# octanis_eps_compact.net
KiCad netlist of a schematic drawn in EAGLE
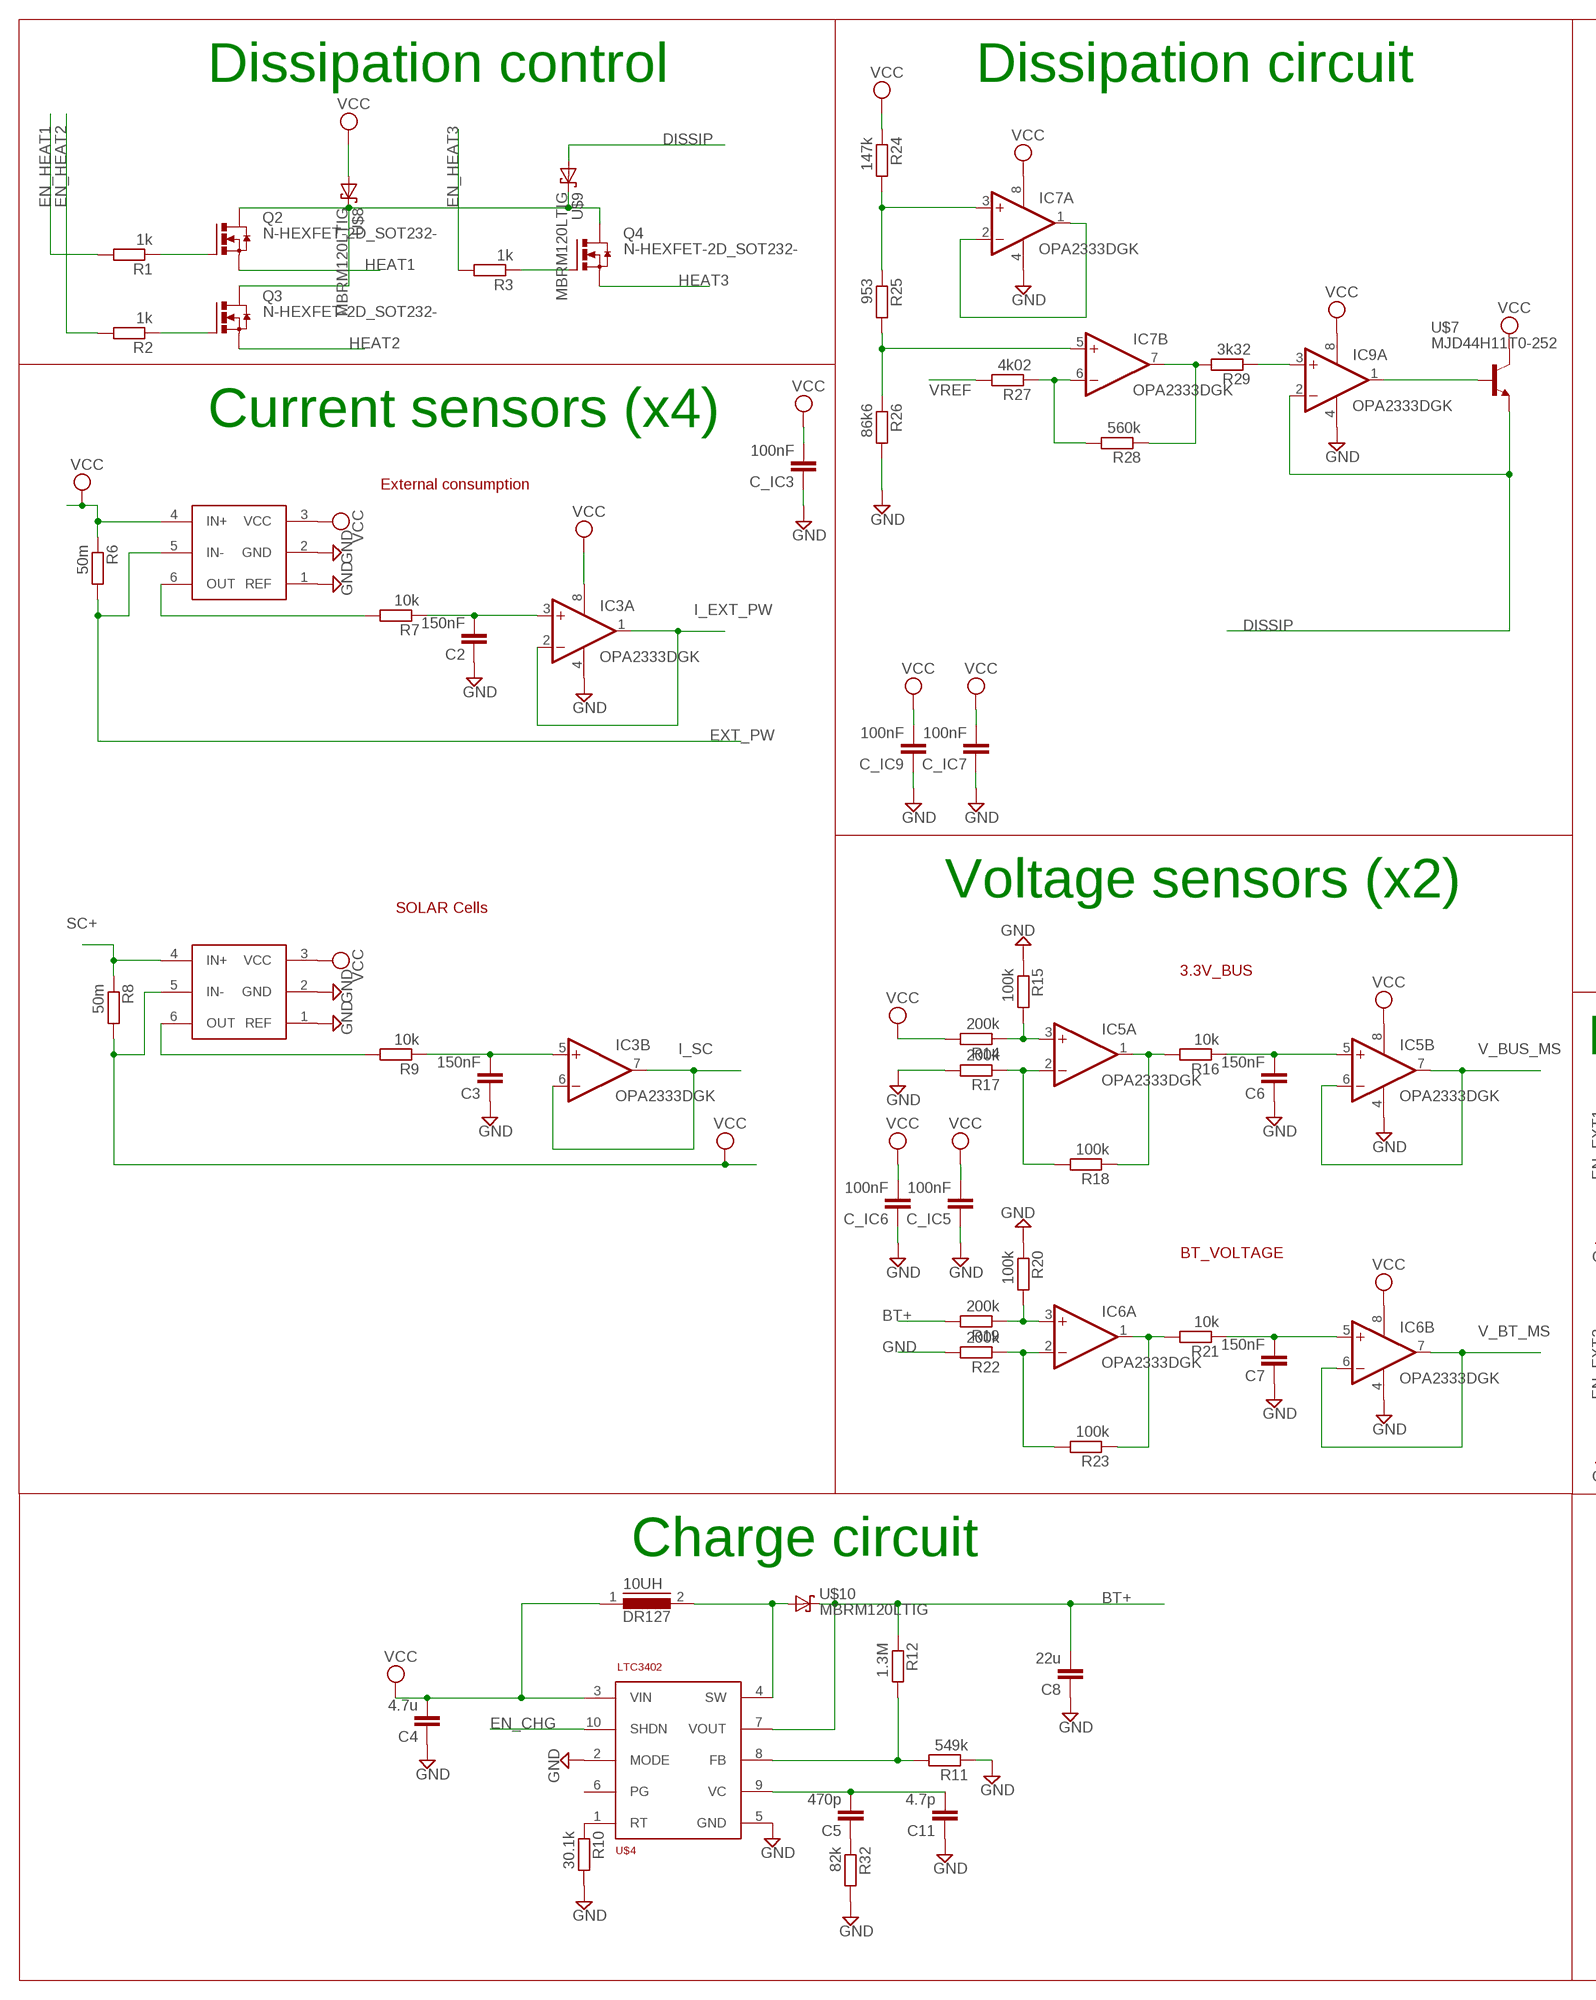
[diagram p0: schematic, sheet 1, part 1 of 2]
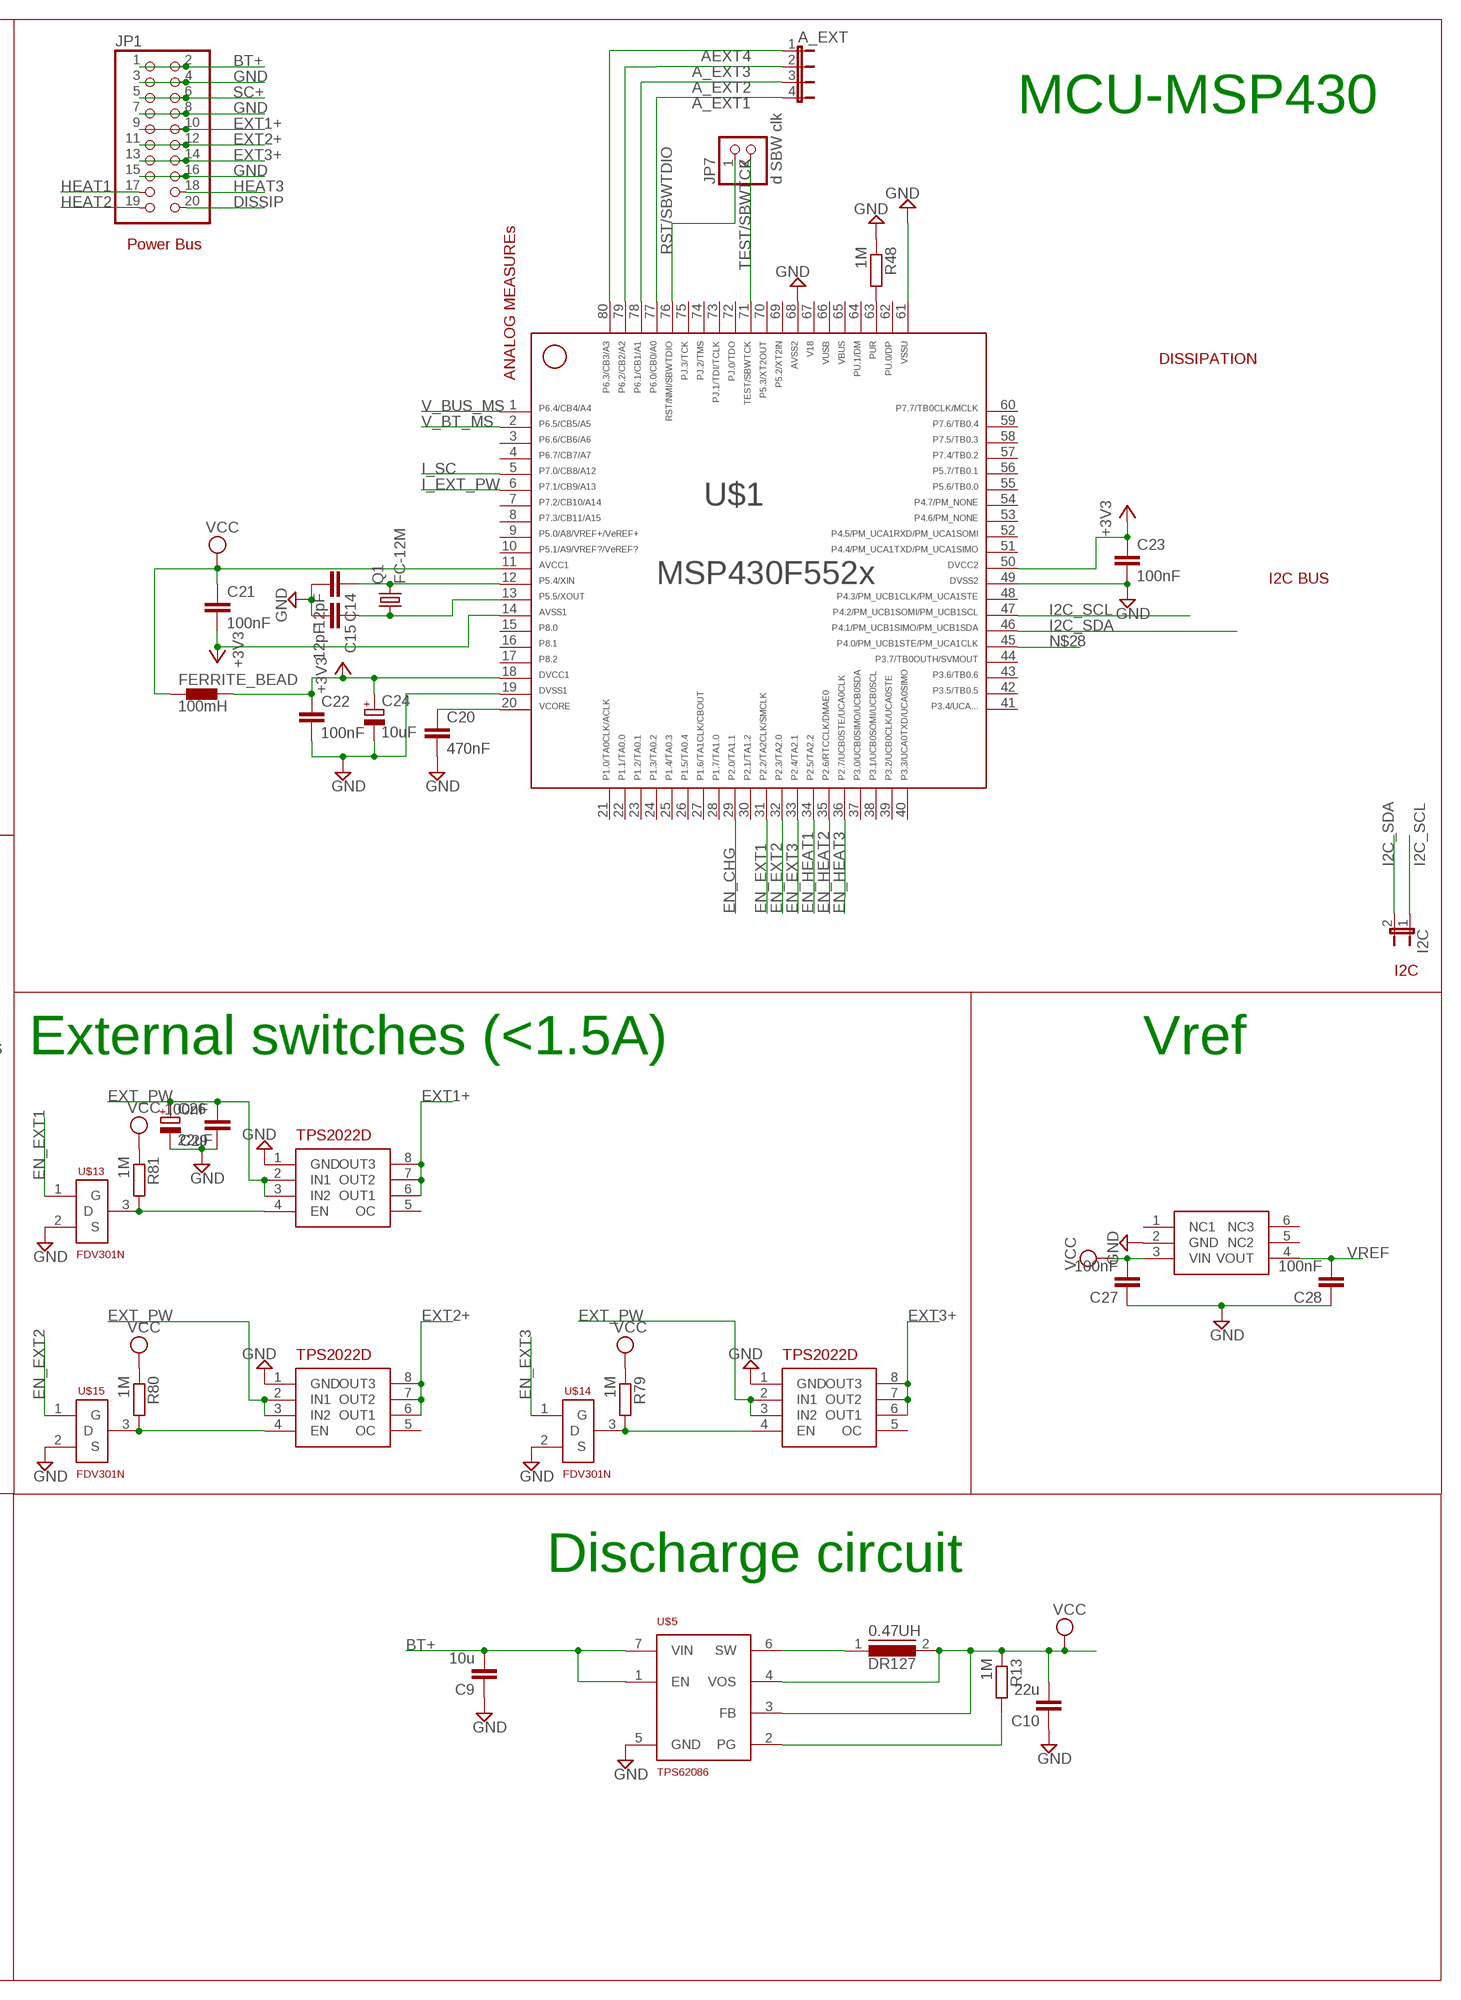
[diagram p1: schematic, sheet 1, part 2 of 2]

(export (version "E")
  (design (tool "Eeschema 10.0.6"))
  (components
    (comp (ref "0.47UH")
      (value "DR127")
      (footprint "eagle-import:DR127")
      (libsource (lib "eagle-import") (part "DR127"))
    )
    (comp (ref "10UH")
      (value "DR127")
      (footprint "eagle-import:DR127")
      (libsource (lib "eagle-import") (part "DR127"))
    )
    (comp (ref "A_EXT")
      (value "JP4E")
      (footprint "eagle-import:JP4")
      (libsource (lib "eagle-import") (part "JP4E"))
    )
    (comp (ref "C2")
      (value "150nF")
      (footprint "eagle-import:C0603")
      (libsource (lib "eagle-import") (part "C-EUC0603"))
    )
    (comp (ref "C3")
      (value "150nF")
      (footprint "eagle-import:C0603")
      (libsource (lib "eagle-import") (part "C-EUC0603"))
    )
    (comp (ref "C4")
      (value "4.7u")
      (footprint "eagle-import:C1206")
      (libsource (lib "eagle-import") (part "C-EUC1206"))
    )
    (comp (ref "C5")
      (value "470p")
      (footprint "eagle-import:C0603")
      (libsource (lib "eagle-import") (part "C-EUC0603"))
    )
    (comp (ref "C6")
      (value "150nF")
      (footprint "eagle-import:C0603")
      (libsource (lib "eagle-import") (part "C-EUC0603"))
    )
    (comp (ref "C7")
      (value "150nF")
      (footprint "eagle-import:C0603")
      (libsource (lib "eagle-import") (part "C-EUC0603"))
    )
    (comp (ref "C8")
      (value "22u")
      (footprint "eagle-import:C0603")
      (libsource (lib "eagle-import") (part "C-EUC0603"))
    )
    (comp (ref "C9")
      (value "10u")
      (footprint "eagle-import:C1206")
      (libsource (lib "eagle-import") (part "C-EUC1206"))
    )
    (comp (ref "C10")
      (value "22u")
      (footprint "eagle-import:C1206")
      (libsource (lib "eagle-import") (part "C-EUC1206"))
    )
    (comp (ref "C11")
      (value "4.7p")
      (footprint "eagle-import:C0603")
      (libsource (lib "eagle-import") (part "C-EUC0603"))
    )
    (comp (ref "C14")
      (value "12pF")
      (footprint "eagle-import:C0603")
      (libsource (lib "eagle-import") (part "C-EUC0603"))
    )
    (comp (ref "C15")
      (value "12pF")
      (footprint "eagle-import:C0603")
      (libsource (lib "eagle-import") (part "C-EUC0603"))
    )
    (comp (ref "C20")
      (value "470nF")
      (footprint "eagle-import:C0603")
      (libsource (lib "eagle-import") (part "C-EUC0603"))
    )
    (comp (ref "C21")
      (value "100nF")
      (footprint "eagle-import:C0603")
      (libsource (lib "eagle-import") (part "C-EUC0603"))
    )
    (comp (ref "C22")
      (value "100nF")
      (footprint "eagle-import:C0603")
      (libsource (lib "eagle-import") (part "C-EUC0603"))
    )
    (comp (ref "C23")
      (value "100nF")
      (footprint "eagle-import:C0603")
      (libsource (lib "eagle-import") (part "C-EUC0603"))
    )
    (comp (ref "C24")
      (value "10uF")
      (footprint "eagle-import:A_3216-18R")
      (libsource (lib "eagle-import") (part "CPOL-EUA/3216-18R"))
    )
    (comp (ref "C26")
      (value "22uF")
      (footprint "eagle-import:A_3216-18R")
      (libsource (lib "eagle-import") (part "CPOL-EUA/3216-18R"))
    )
    (comp (ref "C27")
      (value "100nF")
      (footprint "eagle-import:C0603")
      (libsource (lib "eagle-import") (part "C-EUC0603"))
    )
    (comp (ref "C28")
      (value "100nF")
      (footprint "eagle-import:C0603")
      (libsource (lib "eagle-import") (part "C-EUC0603"))
    )
    (comp (ref "C29")
      (value "100nF")
      (footprint "eagle-import:C0603")
      (libsource (lib "eagle-import") (part "C-EUC0603"))
    )
    (comp (ref "C_IC3")
      (value "100nF")
      (footprint "eagle-import:C0603")
      (libsource (lib "eagle-import") (part "C-EUC0603"))
    )
    (comp (ref "C_IC5")
      (value "100nF")
      (footprint "eagle-import:C0603")
      (libsource (lib "eagle-import") (part "C-EUC0603"))
    )
    (comp (ref "C_IC6")
      (value "100nF")
      (footprint "eagle-import:C0603")
      (libsource (lib "eagle-import") (part "C-EUC0603"))
    )
    (comp (ref "C_IC7")
      (value "100nF")
      (footprint "eagle-import:C0603")
      (libsource (lib "eagle-import") (part "C-EUC0603"))
    )
    (comp (ref "C_IC9")
      (value "100nF")
      (footprint "eagle-import:C0603")
      (libsource (lib "eagle-import") (part "C-EUC0603"))
    )
    (comp (ref "FERRITE_BEAD")
      (value "100mH")
      (footprint "eagle-import:0402")
      (libsource (lib "eagle-import") (part "BLM15HD601SN1"))
    )
    (comp (ref "I2C")
      (value "JP1E")
      (footprint "eagle-import:JP1")
      (libsource (lib "eagle-import") (part "JP1E"))
    )
    (comp (ref "IC3")
      (value "OPA2333DGK")
      (footprint "eagle-import:MSOP08")
      (libsource (lib "eagle-import") (part "OPA2333DGK"))
    )
    (comp (ref "IC5")
      (value "OPA2333DGK")
      (footprint "eagle-import:MSOP08")
      (libsource (lib "eagle-import") (part "OPA2333DGK"))
    )
    (comp (ref "IC6")
      (value "OPA2333DGK")
      (footprint "eagle-import:MSOP08")
      (libsource (lib "eagle-import") (part "OPA2333DGK"))
    )
    (comp (ref "IC7")
      (value "OPA2333DGK")
      (footprint "eagle-import:MSOP08")
      (libsource (lib "eagle-import") (part "OPA2333DGK"))
    )
    (comp (ref "IC9")
      (value "OPA2333DGK")
      (footprint "eagle-import:MSOP08")
      (libsource (lib "eagle-import") (part "OPA2333DGK"))
    )
    (comp (ref "JP1")
      (value "PINHD-2X10")
      (footprint "eagle-import:2X10")
      (libsource (lib "eagle-import") (part "PINHD-2X10"))
    )
    (comp (ref "JP7")
      (value "d SBW clk")
      (footprint "eagle-import:1X02")
      (libsource (lib "eagle-import") (part "PINHD-1X2"))
    )
    (comp (ref "Q1")
      (value "FC-12M")
      (footprint "eagle-import:FC-12M")
      (libsource (lib "eagle-import") (part "FC-12M"))
    )
    (comp (ref "Q2")
      (value "N-HEXFET-2D_SOT232-")
      (footprint "eagle-import:SOT223")
      (libsource (lib "eagle-import") (part "N-HEXFET-2D_?-SOT232"))
    )
    (comp (ref "Q3")
      (value "N-HEXFET-2D_SOT232-")
      (footprint "eagle-import:SOT223")
      (libsource (lib "eagle-import") (part "N-HEXFET-2D_?-SOT232"))
    )
    (comp (ref "Q4")
      (value "N-HEXFET-2D_SOT232-")
      (footprint "eagle-import:SOT223")
      (libsource (lib "eagle-import") (part "N-HEXFET-2D_?-SOT232"))
    )
    (comp (ref "R1")
      (value "1k")
      (footprint "eagle-import:R0603")
      (libsource (lib "eagle-import") (part "R-EU_R0603"))
    )
    (comp (ref "R2")
      (value "1k")
      (footprint "eagle-import:R0603")
      (libsource (lib "eagle-import") (part "R-EU_R0603"))
    )
    (comp (ref "R3")
      (value "1k")
      (footprint "eagle-import:R0603")
      (libsource (lib "eagle-import") (part "R-EU_R0603"))
    )
    (comp (ref "R6")
      (value "50m")
      (footprint "eagle-import:R1206")
      (libsource (lib "eagle-import") (part "R-EU_R1206"))
    )
    (comp (ref "R7")
      (value "10k")
      (footprint "eagle-import:R0603")
      (libsource (lib "eagle-import") (part "R-EU_R0603"))
    )
    (comp (ref "R8")
      (value "50m")
      (footprint "eagle-import:R1206")
      (libsource (lib "eagle-import") (part "R-EU_R1206"))
    )
    (comp (ref "R9")
      (value "10k")
      (footprint "eagle-import:R0603")
      (libsource (lib "eagle-import") (part "R-EU_R0603"))
    )
    (comp (ref "R10")
      (value "30.1k")
      (footprint "eagle-import:R0603")
      (libsource (lib "eagle-import") (part "R-EU_R0603"))
    )
    (comp (ref "R11")
      (value "549k")
      (footprint "eagle-import:R0603")
      (libsource (lib "eagle-import") (part "R-EU_R0603"))
    )
    (comp (ref "R12")
      (value "1.3M")
      (footprint "eagle-import:R0603")
      (libsource (lib "eagle-import") (part "R-EU_R0603"))
    )
    (comp (ref "R13")
      (value "1M")
      (footprint "eagle-import:R0603")
      (libsource (lib "eagle-import") (part "R-EU_R0603"))
    )
    (comp (ref "R14")
      (value "200k")
      (footprint "eagle-import:R0603")
      (libsource (lib "eagle-import") (part "R-EU_R0603"))
    )
    (comp (ref "R15")
      (value "100k")
      (footprint "eagle-import:R0603")
      (libsource (lib "eagle-import") (part "R-EU_R0603"))
    )
    (comp (ref "R16")
      (value "10k")
      (footprint "eagle-import:R0603")
      (libsource (lib "eagle-import") (part "R-EU_R0603"))
    )
    (comp (ref "R17")
      (value "200k")
      (footprint "eagle-import:R0603")
      (libsource (lib "eagle-import") (part "R-EU_R0603"))
    )
    (comp (ref "R18")
      (value "100k")
      (footprint "eagle-import:R0603")
      (libsource (lib "eagle-import") (part "R-EU_R0603"))
    )
    (comp (ref "R19")
      (value "200k")
      (footprint "eagle-import:R0603")
      (libsource (lib "eagle-import") (part "R-EU_R0603"))
    )
    (comp (ref "R20")
      (value "100k")
      (footprint "eagle-import:R0603")
      (libsource (lib "eagle-import") (part "R-EU_R0603"))
    )
    (comp (ref "R21")
      (value "10k")
      (footprint "eagle-import:R0603")
      (libsource (lib "eagle-import") (part "R-EU_R0603"))
    )
    (comp (ref "R22")
      (value "200k")
      (footprint "eagle-import:R0603")
      (libsource (lib "eagle-import") (part "R-EU_R0603"))
    )
    (comp (ref "R23")
      (value "100k")
      (footprint "eagle-import:R0603")
      (libsource (lib "eagle-import") (part "R-EU_R0603"))
    )
    (comp (ref "R24")
      (value "147k")
      (footprint "eagle-import:R0603")
      (libsource (lib "eagle-import") (part "R-EU_R0603"))
    )
    (comp (ref "R25")
      (value "953")
      (footprint "eagle-import:R0603")
      (libsource (lib "eagle-import") (part "R-EU_R0603"))
    )
    (comp (ref "R26")
      (value "86k6")
      (footprint "eagle-import:R0603")
      (libsource (lib "eagle-import") (part "R-EU_R0603"))
    )
    (comp (ref "R27")
      (value "4k02")
      (footprint "eagle-import:R0603")
      (libsource (lib "eagle-import") (part "R-EU_R0603"))
    )
    (comp (ref "R28")
      (value "560k")
      (footprint "eagle-import:R0603")
      (libsource (lib "eagle-import") (part "R-EU_R0603"))
    )
    (comp (ref "R29")
      (value "3k32")
      (footprint "eagle-import:R0603")
      (libsource (lib "eagle-import") (part "R-EU_R0603"))
    )
    (comp (ref "R32")
      (value "82k")
      (footprint "eagle-import:R0603")
      (libsource (lib "eagle-import") (part "R-EU_R0603"))
    )
    (comp (ref "R48")
      (value "1M")
      (footprint "eagle-import:R0603")
      (libsource (lib "eagle-import") (part "R-EU_R0603"))
    )
    (comp (ref "R79")
      (value "1M")
      (footprint "eagle-import:R0603")
      (libsource (lib "eagle-import") (part "R-EU_R0603"))
    )
    (comp (ref "R80")
      (value "1M")
      (footprint "eagle-import:R0603")
      (libsource (lib "eagle-import") (part "R-EU_R0603"))
    )
    (comp (ref "R81")
      (value "1M")
      (footprint "eagle-import:R0603")
      (libsource (lib "eagle-import") (part "R-EU_R0603"))
    )
    (comp (ref "U$1")
      (value "F552X---PN80")
      (footprint "eagle-import:PN80")
      (libsource (lib "eagle-import") (part "F552X---PN80"))
    )
    (comp (ref "U$2")
      (value "INA213")
      (footprint "eagle-import:SC70-6")
      (libsource (lib "eagle-import") (part "INA213"))
    )
    (comp (ref "U$3")
      (value "INA213")
      (footprint "eagle-import:SC70-6")
      (libsource (lib "eagle-import") (part "INA213"))
    )
    (comp (ref "U$4")
      (value "LTC3402")
      (footprint "eagle-import:MSOP10")
      (libsource (lib "eagle-import") (part "LTC3402"))
    )
    (comp (ref "U$5")
      (value "TPS62086")
      (footprint "eagle-import:QFN-7")
      (libsource (lib "eagle-import") (part "TPS62086"))
    )
    (comp (ref "U$7")
      (value "MJD44H11T0-252")
      (footprint "eagle-import:TO252")
      (libsource (lib "eagle-import") (part "MJD44H11T0-252"))
    )
    (comp (ref "U$8")
      (value "MBRM120LTIG")
      (footprint "eagle-import:DO216AA")
      (libsource (lib "eagle-import") (part "MBRM120LTIG"))
    )
    (comp (ref "U$9")
      (value "MBRM120LTIG")
      (footprint "eagle-import:DO216AA")
      (libsource (lib "eagle-import") (part "MBRM120LTIG"))
    )
    (comp (ref "U$10")
      (value "MBRM120LTIG")
      (footprint "eagle-import:DO216AA")
      (libsource (lib "eagle-import") (part "MBRM120LTIG"))
    )
    (comp (ref "U$13")
      (value "FDV301N")
      (footprint "eagle-import:SOT23")
      (libsource (lib "eagle-import") (part "FDV301N"))
    )
    (comp (ref "U$14")
      (value "FDV301N")
      (footprint "eagle-import:SOT23")
      (libsource (lib "eagle-import") (part "FDV301N"))
    )
    (comp (ref "U$15")
      (value "FDV301N")
      (footprint "eagle-import:SOT23")
      (libsource (lib "eagle-import") (part "FDV301N"))
    )
    (comp (ref "U$16")
      (value "TPS2022D")
      (footprint "eagle-import:SO8")
      (libsource (lib "eagle-import") (part "TPS2022D"))
    )
    (comp (ref "U$17")
      (value "TPS2022D")
      (footprint "eagle-import:SO8")
      (libsource (lib "eagle-import") (part "TPS2022D"))
    )
    (comp (ref "U$18")
      (value "TPS2022D")
      (footprint "eagle-import:SO8")
      (libsource (lib "eagle-import") (part "TPS2022D"))
    )
    (comp (ref "U$19")
      (value "ADR127B")
      (footprint "eagle-import:TSOT23-6")
      (libsource (lib "eagle-import") (part "ADR127B"))
    )
  )
  (nets
    (net (code "1") (name "+3V3") (class "Default")
      (node (ref "C21") (pin "2") (pinfunction "2_2") (pintype "passive"))
      (node (ref "C22") (pin "1") (pinfunction "1_1") (pintype "passive"))
      (node (ref "C23") (pin "1") (pinfunction "1_1") (pintype "passive"))
      (node (ref "C24") (pin "+") (pinfunction "+_+") (pintype "passive"))
      (node (ref "FERRITE_BEAD") (pin "2") (pinfunction "2_2") (pintype "passive"))
      (node (ref "U$1") (pin "14") (pinfunction "14_14") (pintype "power_in"))
      (node (ref "U$1") (pin "18") (pinfunction "18_18") (pintype "power_in"))
      (node (ref "U$1") (pin "50") (pinfunction "50_50") (pintype "power_in"))
    )
    (net (code "2") (name "/65") (class "Default")
      (node (ref "U$1") (pin "65") (pinfunction "65_65") (pintype "power_in"))
    )
    (net (code "3") (name "/66") (class "Default")
      (node (ref "U$1") (pin "66") (pinfunction "66_66") (pintype "power_in"))
    )
    (net (code "4") (name "/67") (class "Default")
      (node (ref "U$1") (pin "67") (pinfunction "67_67") (pintype "power_in"))
    )
    (net (code "5") (name "/AEXT4") (class "Default")
      (node (ref "A_EXT") (pin "1") (pinfunction "1_1") (pintype "passive"))
      (node (ref "U$1") (pin "80") (pinfunction "80_80") (pintype "bidirectional"))
    )
    (net (code "6") (name "/A_EXT1") (class "Default")
      (node (ref "A_EXT") (pin "4") (pinfunction "4_4") (pintype "passive"))
      (node (ref "U$1") (pin "77") (pinfunction "77_77") (pintype "bidirectional"))
    )
    (net (code "7") (name "/A_EXT2") (class "Default")
      (node (ref "A_EXT") (pin "3") (pinfunction "3_3") (pintype "passive"))
      (node (ref "U$1") (pin "78") (pinfunction "78_78") (pintype "bidirectional"))
    )
    (net (code "8") (name "/A_EXT3") (class "Default")
      (node (ref "A_EXT") (pin "2") (pinfunction "2_2") (pintype "passive"))
      (node (ref "U$1") (pin "79") (pinfunction "79_79") (pintype "bidirectional"))
    )
    (net (code "9") (name "/BT+") (class "Default")
      (node (ref "C8") (pin "2") (pinfunction "2_2") (pintype "passive"))
      (node (ref "C9") (pin "2") (pinfunction "2_2") (pintype "passive"))
      (node (ref "JP1") (pin "1") (pinfunction "1_1") (pintype "passive"))
      (node (ref "JP1") (pin "2") (pinfunction "2_2") (pintype "passive"))
      (node (ref "R12") (pin "1") (pinfunction "1_1") (pintype "passive"))
      (node (ref "R19") (pin "2") (pinfunction "2_2") (pintype "passive"))
      (node (ref "U$10") (pin "C") (pinfunction "K_C") (pintype "passive"))
      (node (ref "U$4") (pin "7") (pinfunction "VOUT_7") (pintype "bidirectional"))
      (node (ref "U$5") (pin "1") (pinfunction "EN_1") (pintype "bidirectional"))
      (node (ref "U$5") (pin "7") (pinfunction "VIN_7") (pintype "bidirectional"))
    )
    (net (code "10") (name "/DISSIP") (class "Default")
      (node (ref "IC9") (pin "2") (pinfunction "-IN_2") (pintype "input"))
      (node (ref "JP1") (pin "20") (pinfunction "20_20") (pintype "passive"))
      (node (ref "U$7") (pin "3") (pinfunction "E_3") (pintype "passive"))
      (node (ref "U$9") (pin "A") (pinfunction "A_A") (pintype "passive"))
    )
    (net (code "11") (name "/EN_CHG") (class "Default")
      (node (ref "U$1") (pin "29") (pinfunction "29_29") (pintype "bidirectional"))
      (node (ref "U$4") (pin "10") (pinfunction "SHDN_10") (pintype "bidirectional"))
    )
    (net (code "12") (name "/EN_EXT1") (class "Default")
      (node (ref "U$1") (pin "31") (pinfunction "31_31") (pintype "bidirectional"))
      (node (ref "U$13") (pin "1") (pinfunction "G_1") (pintype "bidirectional"))
    )
    (net (code "13") (name "/EN_EXT2") (class "Default")
      (node (ref "U$1") (pin "32") (pinfunction "32_32") (pintype "bidirectional"))
      (node (ref "U$15") (pin "1") (pinfunction "G_1") (pintype "bidirectional"))
    )
    (net (code "14") (name "/EN_EXT3") (class "Default")
      (node (ref "U$1") (pin "33") (pinfunction "33_33") (pintype "bidirectional"))
      (node (ref "U$14") (pin "1") (pinfunction "G_1") (pintype "bidirectional"))
    )
    (net (code "15") (name "/EN_HEAT1") (class "Default")
      (node (ref "R1") (pin "2") (pinfunction "2_2") (pintype "passive"))
      (node (ref "U$1") (pin "34") (pinfunction "34_34") (pintype "bidirectional"))
    )
    (net (code "16") (name "/EN_HEAT2") (class "Default")
      (node (ref "R2") (pin "2") (pinfunction "2_2") (pintype "passive"))
      (node (ref "U$1") (pin "35") (pinfunction "35_35") (pintype "bidirectional"))
    )
    (net (code "17") (name "/EN_HEAT3") (class "Default")
      (node (ref "R3") (pin "2") (pinfunction "2_2") (pintype "passive"))
      (node (ref "U$1") (pin "36") (pinfunction "36_36") (pintype "bidirectional"))
    )
    (net (code "18") (name "/EXT1+") (class "Default")
      (node (ref "JP1") (pin "10") (pinfunction "10_10") (pintype "passive"))
      (node (ref "JP1") (pin "9") (pinfunction "9_9") (pintype "passive"))
      (node (ref "U$16") (pin "6") (pinfunction "OUT1_6") (pintype "bidirectional"))
      (node (ref "U$16") (pin "7") (pinfunction "OUT2_7") (pintype "bidirectional"))
      (node (ref "U$16") (pin "8") (pinfunction "OUT3_8") (pintype "bidirectional"))
    )
    (net (code "19") (name "/EXT2+") (class "Default")
      (node (ref "JP1") (pin "11") (pinfunction "11_11") (pintype "passive"))
      (node (ref "JP1") (pin "12") (pinfunction "12_12") (pintype "passive"))
      (node (ref "U$17") (pin "6") (pinfunction "OUT1_6") (pintype "bidirectional"))
      (node (ref "U$17") (pin "7") (pinfunction "OUT2_7") (pintype "bidirectional"))
      (node (ref "U$17") (pin "8") (pinfunction "OUT3_8") (pintype "bidirectional"))
    )
    (net (code "20") (name "/EXT3+") (class "Default")
      (node (ref "JP1") (pin "13") (pinfunction "13_13") (pintype "passive"))
      (node (ref "JP1") (pin "14") (pinfunction "14_14") (pintype "passive"))
      (node (ref "U$18") (pin "6") (pinfunction "OUT1_6") (pintype "bidirectional"))
      (node (ref "U$18") (pin "7") (pinfunction "OUT2_7") (pintype "bidirectional"))
      (node (ref "U$18") (pin "8") (pinfunction "OUT3_8") (pintype "bidirectional"))
    )
    (net (code "21") (name "/EXT_PW") (class "Default")
      (node (ref "C26") (pin "+") (pinfunction "+_+") (pintype "passive"))
      (node (ref "C29") (pin "2") (pinfunction "2_2") (pintype "passive"))
      (node (ref "R6") (pin "2") (pinfunction "2_2") (pintype "passive"))
      (node (ref "U$16") (pin "2") (pinfunction "IN1_2") (pintype "bidirectional"))
      (node (ref "U$16") (pin "3") (pinfunction "IN2_3") (pintype "bidirectional"))
      (node (ref "U$17") (pin "2") (pinfunction "IN1_2") (pintype "bidirectional"))
      (node (ref "U$17") (pin "3") (pinfunction "IN2_3") (pintype "bidirectional"))
      (node (ref "U$18") (pin "2") (pinfunction "IN1_2") (pintype "bidirectional"))
      (node (ref "U$18") (pin "3") (pinfunction "IN2_3") (pintype "bidirectional"))
      (node (ref "U$2") (pin "5") (pinfunction "IN-_5") (pintype "bidirectional"))
    )
    (net (code "22") (name "/HEAT1") (class "Default")
      (node (ref "JP1") (pin "17") (pinfunction "17_17") (pintype "passive"))
      (node (ref "Q2") (pin "3") (pinfunction "S_3") (pintype "passive"))
    )
    (net (code "23") (name "/HEAT2") (class "Default")
      (node (ref "JP1") (pin "19") (pinfunction "19_19") (pintype "passive"))
      (node (ref "Q3") (pin "3") (pinfunction "S_3") (pintype "passive"))
    )
    (net (code "24") (name "/HEAT3") (class "Default")
      (node (ref "JP1") (pin "18") (pinfunction "18_18") (pintype "passive"))
      (node (ref "Q4") (pin "3") (pinfunction "S_3") (pintype "passive"))
    )
    (net (code "25") (name "/I2C_SCL") (class "Default")
      (node (ref "I2C") (pin "1") (pinfunction "1_1") (pintype "passive"))
      (node (ref "U$1") (pin "47") (pinfunction "47_47") (pintype "bidirectional"))
    )
    (net (code "26") (name "/I2C_SDA") (class "Default")
      (node (ref "I2C") (pin "2") (pinfunction "2_2") (pintype "passive"))
      (node (ref "U$1") (pin "46") (pinfunction "46_46") (pintype "bidirectional"))
    )
    (net (code "27") (name "/I_EXT_PW") (class "Default")
      (node (ref "IC3") (pin "1") (pinfunction "OUT_1") (pintype "output"))
      (node (ref "IC3") (pin "2") (pinfunction "-IN_2") (pintype "input"))
      (node (ref "U$1") (pin "6") (pinfunction "6_6") (pintype "bidirectional"))
    )
    (net (code "28") (name "/I_SC") (class "Default")
      (node (ref "IC3") (pin "6") (pinfunction "-IN_6") (pintype "input"))
      (node (ref "IC3") (pin "7") (pinfunction "OUT_7") (pintype "output"))
      (node (ref "U$1") (pin "5") (pinfunction "5_5") (pintype "bidirectional"))
    )
    (net (code "29") (name "/N$28") (class "Default")
      (node (ref "U$1") (pin "45") (pinfunction "45_45") (pintype "bidirectional"))
    )
    (net (code "30") (name "/RST{slash}SBWTDIO") (class "Default")
      (node (ref "JP7") (pin "1") (pinfunction "1_1") (pintype "passive"))
      (node (ref "U$1") (pin "76") (pinfunction "76_76") (pintype "bidirectional"))
    )
    (net (code "31") (name "/SC+") (class "Default")
      (node (ref "JP1") (pin "5") (pinfunction "5_5") (pintype "passive"))
      (node (ref "JP1") (pin "6") (pinfunction "6_6") (pintype "passive"))
      (node (ref "R8") (pin "1") (pinfunction "1_1") (pintype "passive"))
      (node (ref "U$3") (pin "4") (pinfunction "IN+_4") (pintype "bidirectional"))
    )
    (net (code "32") (name "/TEST{slash}SBWTCK") (class "Default")
      (node (ref "JP7") (pin "2") (pinfunction "2_2") (pintype "passive"))
      (node (ref "U$1") (pin "71") (pinfunction "71_71") (pintype "input"))
    )
    (net (code "33") (name "/VREF") (class "Default")
      (node (ref "C28") (pin "2") (pinfunction "2_2") (pintype "passive"))
      (node (ref "R27") (pin "2") (pinfunction "2_2") (pintype "passive"))
      (node (ref "U$19") (pin "4") (pinfunction "VOUT_4") (pintype "bidirectional"))
    )
    (net (code "34") (name "/V_BT_MS") (class "Default")
      (node (ref "IC6") (pin "6") (pinfunction "-IN_6") (pintype "input"))
      (node (ref "IC6") (pin "7") (pinfunction "OUT_7") (pintype "output"))
      (node (ref "U$1") (pin "2") (pinfunction "2_2") (pintype "bidirectional"))
    )
    (net (code "35") (name "/V_BUS_MS") (class "Default")
      (node (ref "IC5") (pin "6") (pinfunction "-IN_6") (pintype "input"))
      (node (ref "IC5") (pin "7") (pinfunction "OUT_7") (pintype "output"))
      (node (ref "U$1") (pin "1") (pinfunction "1_1") (pintype "bidirectional"))
    )
    (net (code "36") (name "GND") (class "Default")
      (node (ref "C10") (pin "1") (pinfunction "1_1") (pintype "passive"))
      (node (ref "C11") (pin "1") (pinfunction "1_1") (pintype "passive"))
      (node (ref "C14") (pin "2") (pinfunction "2_2") (pintype "passive"))
      (node (ref "C15") (pin "2") (pinfunction "2_2") (pintype "passive"))
      (node (ref "C2") (pin "1") (pinfunction "1_1") (pintype "passive"))
      (node (ref "C20") (pin "2") (pinfunction "2_2") (pintype "passive"))
      (node (ref "C22") (pin "2") (pinfunction "2_2") (pintype "passive"))
      (node (ref "C23") (pin "2") (pinfunction "2_2") (pintype "passive"))
      (node (ref "C24") (pin "-") (pinfunction "-_-") (pintype "passive"))
      (node (ref "C26") (pin "-") (pinfunction "-_-") (pintype "passive"))
      (node (ref "C27") (pin "1") (pinfunction "1_1") (pintype "passive"))
      (node (ref "C28") (pin "1") (pinfunction "1_1") (pintype "passive"))
      (node (ref "C29") (pin "1") (pinfunction "1_1") (pintype "passive"))
      (node (ref "C3") (pin "1") (pinfunction "1_1") (pintype "passive"))
      (node (ref "C4") (pin "1") (pinfunction "1_1") (pintype "passive"))
      (node (ref "C6") (pin "1") (pinfunction "1_1") (pintype "passive"))
      (node (ref "C7") (pin "1") (pinfunction "1_1") (pintype "passive"))
      (node (ref "C8") (pin "1") (pinfunction "1_1") (pintype "passive"))
      (node (ref "C9") (pin "1") (pinfunction "1_1") (pintype "passive"))
      (node (ref "C_IC3") (pin "1") (pinfunction "1_1") (pintype "passive"))
      (node (ref "C_IC5") (pin "1") (pinfunction "1_1") (pintype "passive"))
      (node (ref "C_IC6") (pin "1") (pinfunction "1_1") (pintype "passive"))
      (node (ref "C_IC7") (pin "1") (pinfunction "1_1") (pintype "passive"))
      (node (ref "C_IC9") (pin "1") (pinfunction "1_1") (pintype "passive"))
      (node (ref "IC3") (pin "4") (pinfunction "V-_4") (pintype "power_in"))
      (node (ref "IC5") (pin "4") (pinfunction "V-_4") (pintype "power_in"))
      (node (ref "IC6") (pin "4") (pinfunction "V-_4") (pintype "power_in"))
      (node (ref "IC7") (pin "4") (pinfunction "V-_4") (pintype "power_in"))
      (node (ref "IC9") (pin "4") (pinfunction "V-_4") (pintype "power_in"))
      (node (ref "JP1") (pin "15") (pinfunction "15_15") (pintype "passive"))
      (node (ref "JP1") (pin "16") (pinfunction "16_16") (pintype "passive"))
      (node (ref "JP1") (pin "3") (pinfunction "3_3") (pintype "passive"))
      (node (ref "JP1") (pin "4") (pinfunction "4_4") (pintype "passive"))
      (node (ref "JP1") (pin "7") (pinfunction "7_7") (pintype "passive"))
      (node (ref "JP1") (pin "8") (pinfunction "8_8") (pintype "passive"))
      (node (ref "R10") (pin "2") (pinfunction "2_2") (pintype "passive"))
      (node (ref "R11") (pin "1") (pinfunction "1_1") (pintype "passive"))
      (node (ref "R15") (pin "1") (pinfunction "1_1") (pintype "passive"))
      (node (ref "R17") (pin "2") (pinfunction "2_2") (pintype "passive"))
      (node (ref "R20") (pin "1") (pinfunction "1_1") (pintype "passive"))
      (node (ref "R22") (pin "2") (pinfunction "2_2") (pintype "passive"))
      (node (ref "R26") (pin "2") (pinfunction "2_2") (pintype "passive"))
      (node (ref "R32") (pin "2") (pinfunction "2_2") (pintype "passive"))
      (node (ref "R48") (pin "1") (pinfunction "1_1") (pintype "passive"))
      (node (ref "U$1") (pin "19") (pinfunction "19_19") (pintype "power_in"))
      (node (ref "U$1") (pin "49") (pinfunction "49_49") (pintype "power_in"))
      (node (ref "U$1") (pin "61") (pinfunction "61_61") (pintype "power_in"))
      (node (ref "U$1") (pin "68") (pinfunction "68_68") (pintype "power_in"))
      (node (ref "U$13") (pin "2") (pinfunction "S_2") (pintype "bidirectional"))
      (node (ref "U$14") (pin "2") (pinfunction "S_2") (pintype "bidirectional"))
      (node (ref "U$15") (pin "2") (pinfunction "S_2") (pintype "bidirectional"))
      (node (ref "U$16") (pin "1") (pinfunction "GND_1") (pintype "bidirectional"))
      (node (ref "U$17") (pin "1") (pinfunction "GND_1") (pintype "bidirectional"))
      (node (ref "U$18") (pin "1") (pinfunction "GND_1") (pintype "bidirectional"))
      (node (ref "U$19") (pin "2") (pinfunction "GND_2") (pintype "bidirectional"))
      (node (ref "U$2") (pin "1") (pinfunction "REF_1") (pintype "bidirectional"))
      (node (ref "U$2") (pin "2") (pinfunction "GND_2") (pintype "bidirectional"))
      (node (ref "U$3") (pin "1") (pinfunction "REF_1") (pintype "bidirectional"))
      (node (ref "U$3") (pin "2") (pinfunction "GND_2") (pintype "bidirectional"))
      (node (ref "U$4") (pin "2") (pinfunction "MODE_2") (pintype "bidirectional"))
      (node (ref "U$4") (pin "5") (pinfunction "GND_5") (pintype "bidirectional"))
      (node (ref "U$5") (pin "5") (pinfunction "GND_5") (pintype "bidirectional"))
    )
    (net (code "37") (name "Net-(C5-Pad1)") (class "Default")
      (node (ref "C5") (pin "1") (pinfunction "1_1") (pintype "passive"))
      (node (ref "R32") (pin "1") (pinfunction "1_1") (pintype "passive"))
    )
    (net (code "38") (name "Net-(C14-Pad1)") (class "Default")
      (node (ref "C14") (pin "1") (pinfunction "1_1") (pintype "passive"))
      (node (ref "Q1") (pin "2") (pinfunction "2_2") (pintype "passive"))
      (node (ref "U$1") (pin "12") (pinfunction "12_12") (pintype "bidirectional"))
    )
    (net (code "39") (name "Net-(C15-Pad1)") (class "Default")
      (node (ref "C15") (pin "1") (pinfunction "1_1") (pintype "passive"))
      (node (ref "Q1") (pin "1") (pinfunction "1_1") (pintype "passive"))
      (node (ref "U$1") (pin "13") (pinfunction "13_13") (pintype "bidirectional"))
    )
    (net (code "40") (name "Net-(C20-Pad1)") (class "Default")
      (node (ref "C20") (pin "1") (pinfunction "1_1") (pintype "passive"))
      (node (ref "U$1") (pin "20") (pinfunction "20_20") (pintype "power_in"))
    )
    (net (code "41") (name "Net-(IC3A-+IN)") (class "Default")
      (node (ref "C2") (pin "2") (pinfunction "2_2") (pintype "passive"))
      (node (ref "IC3") (pin "3") (pinfunction "+IN_3") (pintype "input"))
      (node (ref "R7") (pin "1") (pinfunction "1_1") (pintype "passive"))
    )
    (net (code "42") (name "Net-(IC3B-+IN)") (class "Default")
      (node (ref "C3") (pin "2") (pinfunction "2_2") (pintype "passive"))
      (node (ref "IC3") (pin "5") (pinfunction "+IN_5") (pintype "input"))
      (node (ref "R9") (pin "1") (pinfunction "1_1") (pintype "passive"))
    )
    (net (code "43") (name "Net-(IC5A-+IN)") (class "Default")
      (node (ref "IC5") (pin "3") (pinfunction "+IN_3") (pintype "input"))
      (node (ref "R14") (pin "1") (pinfunction "1_1") (pintype "passive"))
      (node (ref "R15") (pin "2") (pinfunction "2_2") (pintype "passive"))
    )
    (net (code "44") (name "Net-(IC5A--IN)") (class "Default")
      (node (ref "IC5") (pin "2") (pinfunction "-IN_2") (pintype "input"))
      (node (ref "R17") (pin "1") (pinfunction "1_1") (pintype "passive"))
      (node (ref "R18") (pin "2") (pinfunction "2_2") (pintype "passive"))
    )
    (net (code "45") (name "Net-(IC5A-OUT)") (class "Default")
      (node (ref "IC5") (pin "1") (pinfunction "OUT_1") (pintype "output"))
      (node (ref "R16") (pin "2") (pinfunction "2_2") (pintype "passive"))
      (node (ref "R18") (pin "1") (pinfunction "1_1") (pintype "passive"))
    )
    (net (code "46") (name "Net-(IC5B-+IN)") (class "Default")
      (node (ref "C6") (pin "2") (pinfunction "2_2") (pintype "passive"))
      (node (ref "IC5") (pin "5") (pinfunction "+IN_5") (pintype "input"))
      (node (ref "R16") (pin "1") (pinfunction "1_1") (pintype "passive"))
    )
    (net (code "47") (name "Net-(IC6A-+IN)") (class "Default")
      (node (ref "IC6") (pin "3") (pinfunction "+IN_3") (pintype "input"))
      (node (ref "R19") (pin "1") (pinfunction "1_1") (pintype "passive"))
      (node (ref "R20") (pin "2") (pinfunction "2_2") (pintype "passive"))
    )
    (net (code "48") (name "Net-(IC6A--IN)") (class "Default")
      (node (ref "IC6") (pin "2") (pinfunction "-IN_2") (pintype "input"))
      (node (ref "R22") (pin "1") (pinfunction "1_1") (pintype "passive"))
      (node (ref "R23") (pin "2") (pinfunction "2_2") (pintype "passive"))
    )
    (net (code "49") (name "Net-(IC6A-OUT)") (class "Default")
      (node (ref "IC6") (pin "1") (pinfunction "OUT_1") (pintype "output"))
      (node (ref "R21") (pin "2") (pinfunction "2_2") (pintype "passive"))
      (node (ref "R23") (pin "1") (pinfunction "1_1") (pintype "passive"))
    )
    (net (code "50") (name "Net-(IC6B-+IN)") (class "Default")
      (node (ref "C7") (pin "2") (pinfunction "2_2") (pintype "passive"))
      (node (ref "IC6") (pin "5") (pinfunction "+IN_5") (pintype "input"))
      (node (ref "R21") (pin "1") (pinfunction "1_1") (pintype "passive"))
    )
    (net (code "51") (name "Net-(IC7A-+IN)") (class "Default")
      (node (ref "IC7") (pin "3") (pinfunction "+IN_3") (pintype "input"))
      (node (ref "R24") (pin "2") (pinfunction "2_2") (pintype "passive"))
      (node (ref "R25") (pin "1") (pinfunction "1_1") (pintype "passive"))
    )
    (net (code "52") (name "Net-(IC7A--IN)") (class "Default")
      (node (ref "IC7") (pin "1") (pinfunction "OUT_1") (pintype "output"))
      (node (ref "IC7") (pin "2") (pinfunction "-IN_2") (pintype "input"))
    )
    (net (code "53") (name "Net-(IC7B-+IN)") (class "Default")
      (node (ref "IC7") (pin "5") (pinfunction "+IN_5") (pintype "input"))
      (node (ref "R25") (pin "2") (pinfunction "2_2") (pintype "passive"))
      (node (ref "R26") (pin "1") (pinfunction "1_1") (pintype "passive"))
    )
    (net (code "54") (name "Net-(IC7B--IN)") (class "Default")
      (node (ref "IC7") (pin "6") (pinfunction "-IN_6") (pintype "input"))
      (node (ref "R27") (pin "1") (pinfunction "1_1") (pintype "passive"))
      (node (ref "R28") (pin "2") (pinfunction "2_2") (pintype "passive"))
    )
    (net (code "55") (name "Net-(IC7B-OUT)") (class "Default")
      (node (ref "IC7") (pin "7") (pinfunction "OUT_7") (pintype "output"))
      (node (ref "R28") (pin "1") (pinfunction "1_1") (pintype "passive"))
      (node (ref "R29") (pin "2") (pinfunction "2_2") (pintype "passive"))
    )
    (net (code "56") (name "Net-(IC9A-+IN)") (class "Default")
      (node (ref "IC9") (pin "3") (pinfunction "+IN_3") (pintype "input"))
      (node (ref "R29") (pin "1") (pinfunction "1_1") (pintype "passive"))
    )
    (net (code "57") (name "Net-(IC9A-OUT)") (class "Default")
      (node (ref "IC9") (pin "1") (pinfunction "OUT_1") (pintype "output"))
      (node (ref "U$7") (pin "1") (pinfunction "B_1") (pintype "passive"))
    )
    (net (code "58") (name "Net-(Q2-G)") (class "Default")
      (node (ref "Q2") (pin "1") (pinfunction "G_1") (pintype "passive"))
      (node (ref "R1") (pin "1") (pinfunction "1_1") (pintype "passive"))
    )
    (net (code "59") (name "Net-(Q3-G)") (class "Default")
      (node (ref "Q3") (pin "1") (pinfunction "G_1") (pintype "passive"))
      (node (ref "R2") (pin "1") (pinfunction "1_1") (pintype "passive"))
    )
    (net (code "60") (name "Net-(Q4-G)") (class "Default")
      (node (ref "Q4") (pin "1") (pinfunction "G_1") (pintype "passive"))
      (node (ref "R3") (pin "1") (pinfunction "1_1") (pintype "passive"))
    )
    (net (code "61") (name "Net-(R48-Pad2)") (class "Default")
      (node (ref "R48") (pin "2") (pinfunction "2_2") (pintype "passive"))
      (node (ref "U$1") (pin "63") (pinfunction "63_63") (pintype "bidirectional"))
    )
    (net (code "62") (name "Net-(U$2-OUT)") (class "Default")
      (node (ref "R7") (pin "2") (pinfunction "2_2") (pintype "passive"))
      (node (ref "U$2") (pin "6") (pinfunction "OUT_6") (pintype "bidirectional"))
    )
    (net (code "63") (name "Net-(U$3-OUT)") (class "Default")
      (node (ref "R9") (pin "2") (pinfunction "2_2") (pintype "passive"))
      (node (ref "U$3") (pin "6") (pinfunction "OUT_6") (pintype "bidirectional"))
    )
    (net (code "64") (name "Net-(U$4-FB)") (class "Default")
      (node (ref "R11") (pin "2") (pinfunction "2_2") (pintype "passive"))
      (node (ref "R12") (pin "2") (pinfunction "2_2") (pintype "passive"))
      (node (ref "U$4") (pin "8") (pinfunction "FB_8") (pintype "bidirectional"))
    )
    (net (code "65") (name "Net-(U$4-RT)") (class "Default")
      (node (ref "R10") (pin "1") (pinfunction "1_1") (pintype "passive"))
      (node (ref "U$4") (pin "1") (pinfunction "RT_1") (pintype "bidirectional"))
    )
    (net (code "66") (name "Net-(U$4-SW)") (class "Default")
      (node (ref "10UH") (pin "2") (pinfunction "2_2") (pintype "passive"))
      (node (ref "U$10") (pin "A") (pinfunction "A_A") (pintype "passive"))
      (node (ref "U$4") (pin "4") (pinfunction "SW_4") (pintype "bidirectional"))
    )
    (net (code "67") (name "Net-(U$4-VC)") (class "Default")
      (node (ref "C11") (pin "2") (pinfunction "2_2") (pintype "passive"))
      (node (ref "C5") (pin "2") (pinfunction "2_2") (pintype "passive"))
      (node (ref "U$4") (pin "9") (pinfunction "VC_9") (pintype "bidirectional"))
    )
    (net (code "68") (name "Net-(U$5-PG)") (class "Default")
      (node (ref "R13") (pin "2") (pinfunction "2_2") (pintype "passive"))
      (node (ref "U$5") (pin "2") (pinfunction "PG_2") (pintype "bidirectional"))
    )
    (net (code "69") (name "Net-(U$5-SW)") (class "Default")
      (node (ref "0.47UH") (pin "1") (pinfunction "1_1") (pintype "passive"))
      (node (ref "U$5") (pin "6") (pinfunction "SW_6") (pintype "bidirectional"))
    )
    (net (code "70") (name "Net-(U$8-K)") (class "Default")
      (node (ref "Q2") (pin "2") (pinfunction "D_2") (pintype "passive"))
      (node (ref "Q2") (pin "4") (pinfunction "D_4") (pintype "passive"))
      (node (ref "Q3") (pin "2") (pinfunction "D_2") (pintype "passive"))
      (node (ref "Q3") (pin "4") (pinfunction "D_4") (pintype "passive"))
      (node (ref "Q4") (pin "2") (pinfunction "D_2") (pintype "passive"))
      (node (ref "Q4") (pin "4") (pinfunction "D_4") (pintype "passive"))
      (node (ref "U$8") (pin "C") (pinfunction "K_C") (pintype "passive"))
      (node (ref "U$9") (pin "C") (pinfunction "K_C") (pintype "passive"))
    )
    (net (code "71") (name "Net-(U$13-D)") (class "Default")
      (node (ref "R81") (pin "2") (pinfunction "2_2") (pintype "passive"))
      (node (ref "U$13") (pin "3") (pinfunction "D_3") (pintype "bidirectional"))
      (node (ref "U$16") (pin "4") (pinfunction "EN_4") (pintype "bidirectional"))
    )
    (net (code "72") (name "Net-(U$14-D)") (class "Default")
      (node (ref "R79") (pin "2") (pinfunction "2_2") (pintype "passive"))
      (node (ref "U$14") (pin "3") (pinfunction "D_3") (pintype "bidirectional"))
      (node (ref "U$18") (pin "4") (pinfunction "EN_4") (pintype "bidirectional"))
    )
    (net (code "73") (name "Net-(U$15-D)") (class "Default")
      (node (ref "R80") (pin "2") (pinfunction "2_2") (pintype "passive"))
      (node (ref "U$15") (pin "3") (pinfunction "D_3") (pintype "bidirectional"))
      (node (ref "U$17") (pin "4") (pinfunction "EN_4") (pintype "bidirectional"))
    )
    (net (code "74") (name "VCC") (class "Default")
      (node (ref "0.47UH") (pin "2") (pinfunction "2_2") (pintype "passive"))
      (node (ref "10UH") (pin "1") (pinfunction "1_1") (pintype "passive"))
      (node (ref "C10") (pin "2") (pinfunction "2_2") (pintype "passive"))
      (node (ref "C21") (pin "1") (pinfunction "1_1") (pintype "passive"))
      (node (ref "C27") (pin "2") (pinfunction "2_2") (pintype "passive"))
      (node (ref "C4") (pin "2") (pinfunction "2_2") (pintype "passive"))
      (node (ref "C_IC3") (pin "2") (pinfunction "2_2") (pintype "passive"))
      (node (ref "C_IC5") (pin "2") (pinfunction "2_2") (pintype "passive"))
      (node (ref "C_IC6") (pin "2") (pinfunction "2_2") (pintype "passive"))
      (node (ref "C_IC7") (pin "2") (pinfunction "2_2") (pintype "passive"))
      (node (ref "C_IC9") (pin "2") (pinfunction "2_2") (pintype "passive"))
      (node (ref "FERRITE_BEAD") (pin "1") (pinfunction "1_1") (pintype "passive"))
      (node (ref "IC3") (pin "8") (pinfunction "V+_8") (pintype "power_in"))
      (node (ref "IC5") (pin "8") (pinfunction "V+_8") (pintype "power_in"))
      (node (ref "IC6") (pin "8") (pinfunction "V+_8") (pintype "power_in"))
      (node (ref "IC7") (pin "8") (pinfunction "V+_8") (pintype "power_in"))
      (node (ref "IC9") (pin "8") (pinfunction "V+_8") (pintype "power_in"))
      (node (ref "R13") (pin "1") (pinfunction "1_1") (pintype "passive"))
      (node (ref "R14") (pin "2") (pinfunction "2_2") (pintype "passive"))
      (node (ref "R24") (pin "1") (pinfunction "1_1") (pintype "passive"))
      (node (ref "R6") (pin "1") (pinfunction "1_1") (pintype "passive"))
      (node (ref "R79") (pin "1") (pinfunction "1_1") (pintype "passive"))
      (node (ref "R8") (pin "2") (pinfunction "2_2") (pintype "passive"))
      (node (ref "R80") (pin "1") (pinfunction "1_1") (pintype "passive"))
      (node (ref "R81") (pin "1") (pinfunction "1_1") (pintype "passive"))
      (node (ref "U$1") (pin "11") (pinfunction "11_11") (pintype "power_in"))
      (node (ref "U$19") (pin "3") (pinfunction "VIN_3") (pintype "bidirectional"))
      (node (ref "U$2") (pin "3") (pinfunction "VCC_3") (pintype "bidirectional"))
      (node (ref "U$2") (pin "4") (pinfunction "IN+_4") (pintype "bidirectional"))
      (node (ref "U$3") (pin "3") (pinfunction "VCC_3") (pintype "bidirectional"))
      (node (ref "U$3") (pin "5") (pinfunction "IN-_5") (pintype "bidirectional"))
      (node (ref "U$4") (pin "3") (pinfunction "VIN_3") (pintype "bidirectional"))
      (node (ref "U$5") (pin "3") (pinfunction "FB_3") (pintype "bidirectional"))
      (node (ref "U$5") (pin "4") (pinfunction "VOS_4") (pintype "bidirectional"))
      (node (ref "U$7") (pin "2") (pinfunction "C_2") (pintype "passive"))
      (node (ref "U$8") (pin "A") (pinfunction "A_A") (pintype "passive"))
    )
    (net (code "75") (name "unconnected-(U$1-Pad3)") (class "Default")
      (node (ref "U$1") (pin "3") (pinfunction "3_3") (pintype "bidirectional"))
    )
    (net (code "76") (name "unconnected-(U$1-Pad4)") (class "Default")
      (node (ref "U$1") (pin "4") (pinfunction "4_4") (pintype "bidirectional"))
    )
    (net (code "77") (name "unconnected-(U$1-Pad7)") (class "Default")
      (node (ref "U$1") (pin "7") (pinfunction "7_7") (pintype "bidirectional"))
    )
    (net (code "78") (name "unconnected-(U$1-Pad8)") (class "Default")
      (node (ref "U$1") (pin "8") (pinfunction "8_8") (pintype "bidirectional"))
    )
    (net (code "79") (name "unconnected-(U$1-Pad9)") (class "Default")
      (node (ref "U$1") (pin "9") (pinfunction "9_9") (pintype "bidirectional"))
    )
    (net (code "80") (name "unconnected-(U$1-Pad10)") (class "Default")
      (node (ref "U$1") (pin "10") (pinfunction "10_10") (pintype "bidirectional"))
    )
    (net (code "81") (name "unconnected-(U$1-Pad15)") (class "Default")
      (node (ref "U$1") (pin "15") (pinfunction "15_15") (pintype "bidirectional"))
    )
    (net (code "82") (name "unconnected-(U$1-Pad16)") (class "Default")
      (node (ref "U$1") (pin "16") (pinfunction "16_16") (pintype "bidirectional"))
    )
    (net (code "83") (name "unconnected-(U$1-Pad17)") (class "Default")
      (node (ref "U$1") (pin "17") (pinfunction "17_17") (pintype "bidirectional"))
    )
    (net (code "84") (name "unconnected-(U$1-Pad21)") (class "Default")
      (node (ref "U$1") (pin "21") (pinfunction "21_21") (pintype "bidirectional"))
    )
    (net (code "85") (name "unconnected-(U$1-Pad22)") (class "Default")
      (node (ref "U$1") (pin "22") (pinfunction "22_22") (pintype "bidirectional"))
    )
    (net (code "86") (name "unconnected-(U$1-Pad23)") (class "Default")
      (node (ref "U$1") (pin "23") (pinfunction "23_23") (pintype "bidirectional"))
    )
    (net (code "87") (name "unconnected-(U$1-Pad24)") (class "Default")
      (node (ref "U$1") (pin "24") (pinfunction "24_24") (pintype "bidirectional"))
    )
    (net (code "88") (name "unconnected-(U$1-Pad25)") (class "Default")
      (node (ref "U$1") (pin "25") (pinfunction "25_25") (pintype "bidirectional"))
    )
    (net (code "89") (name "unconnected-(U$1-Pad26)") (class "Default")
      (node (ref "U$1") (pin "26") (pinfunction "26_26") (pintype "bidirectional"))
    )
    (net (code "90") (name "unconnected-(U$1-Pad27)") (class "Default")
      (node (ref "U$1") (pin "27") (pinfunction "27_27") (pintype "bidirectional"))
    )
    (net (code "91") (name "unconnected-(U$1-Pad28)") (class "Default")
      (node (ref "U$1") (pin "28") (pinfunction "28_28") (pintype "bidirectional"))
    )
    (net (code "92") (name "unconnected-(U$1-Pad30)") (class "Default")
      (node (ref "U$1") (pin "30") (pinfunction "30_30") (pintype "bidirectional"))
    )
    (net (code "93") (name "unconnected-(U$1-Pad37)") (class "Default")
      (node (ref "U$1") (pin "37") (pinfunction "37_37") (pintype "bidirectional"))
    )
    (net (code "94") (name "unconnected-(U$1-Pad38)") (class "Default")
      (node (ref "U$1") (pin "38") (pinfunction "38_38") (pintype "bidirectional"))
    )
    (net (code "95") (name "unconnected-(U$1-Pad39)") (class "Default")
      (node (ref "U$1") (pin "39") (pinfunction "39_39") (pintype "bidirectional"))
    )
    (net (code "96") (name "unconnected-(U$1-Pad40)") (class "Default")
      (node (ref "U$1") (pin "40") (pinfunction "40_40") (pintype "bidirectional"))
    )
    (net (code "97") (name "unconnected-(U$1-Pad41)") (class "Default")
      (node (ref "U$1") (pin "41") (pinfunction "41_41") (pintype "bidirectional"))
    )
    (net (code "98") (name "unconnected-(U$1-Pad42)") (class "Default")
      (node (ref "U$1") (pin "42") (pinfunction "42_42") (pintype "bidirectional"))
    )
    (net (code "99") (name "unconnected-(U$1-Pad43)") (class "Default")
      (node (ref "U$1") (pin "43") (pinfunction "43_43") (pintype "bidirectional"))
    )
    (net (code "100") (name "unconnected-(U$1-Pad44)") (class "Default")
      (node (ref "U$1") (pin "44") (pinfunction "44_44") (pintype "bidirectional"))
    )
    (net (code "101") (name "unconnected-(U$1-Pad48)") (class "Default")
      (node (ref "U$1") (pin "48") (pinfunction "48_48") (pintype "bidirectional"))
    )
    (net (code "102") (name "unconnected-(U$1-Pad51)") (class "Default")
      (node (ref "U$1") (pin "51") (pinfunction "51_51") (pintype "bidirectional"))
    )
    (net (code "103") (name "unconnected-(U$1-Pad52)") (class "Default")
      (node (ref "U$1") (pin "52") (pinfunction "52_52") (pintype "bidirectional"))
    )
    (net (code "104") (name "unconnected-(U$1-Pad53)") (class "Default")
      (node (ref "U$1") (pin "53") (pinfunction "53_53") (pintype "bidirectional"))
    )
    (net (code "105") (name "unconnected-(U$1-Pad54)") (class "Default")
      (node (ref "U$1") (pin "54") (pinfunction "54_54") (pintype "bidirectional"))
    )
    (net (code "106") (name "unconnected-(U$1-Pad55)") (class "Default")
      (node (ref "U$1") (pin "55") (pinfunction "55_55") (pintype "bidirectional"))
    )
    (net (code "107") (name "unconnected-(U$1-Pad56)") (class "Default")
      (node (ref "U$1") (pin "56") (pinfunction "56_56") (pintype "bidirectional"))
    )
    (net (code "108") (name "unconnected-(U$1-Pad57)") (class "Default")
      (node (ref "U$1") (pin "57") (pinfunction "57_57") (pintype "bidirectional"))
    )
    (net (code "109") (name "unconnected-(U$1-Pad58)") (class "Default")
      (node (ref "U$1") (pin "58") (pinfunction "58_58") (pintype "bidirectional"))
    )
    (net (code "110") (name "unconnected-(U$1-Pad59)") (class "Default")
      (node (ref "U$1") (pin "59") (pinfunction "59_59") (pintype "bidirectional"))
    )
    (net (code "111") (name "unconnected-(U$1-Pad60)") (class "Default")
      (node (ref "U$1") (pin "60") (pinfunction "60_60") (pintype "bidirectional"))
    )
    (net (code "112") (name "unconnected-(U$1-Pad62)") (class "Default")
      (node (ref "U$1") (pin "62") (pinfunction "62_62") (pintype "bidirectional"))
    )
    (net (code "113") (name "unconnected-(U$1-Pad64)") (class "Default")
      (node (ref "U$1") (pin "64") (pinfunction "64_64") (pintype "bidirectional"))
    )
    (net (code "114") (name "unconnected-(U$1-Pad69)") (class "Default")
      (node (ref "U$1") (pin "69") (pinfunction "69_69") (pintype "bidirectional"))
    )
    (net (code "115") (name "unconnected-(U$1-Pad70)") (class "Default")
      (node (ref "U$1") (pin "70") (pinfunction "70_70") (pintype "bidirectional"))
    )
    (net (code "116") (name "unconnected-(U$1-Pad72)") (class "Default")
      (node (ref "U$1") (pin "72") (pinfunction "72_72") (pintype "bidirectional"))
    )
    (net (code "117") (name "unconnected-(U$1-Pad73)") (class "Default")
      (node (ref "U$1") (pin "73") (pinfunction "73_73") (pintype "bidirectional"))
    )
    (net (code "118") (name "unconnected-(U$1-Pad74)") (class "Default")
      (node (ref "U$1") (pin "74") (pinfunction "74_74") (pintype "bidirectional"))
    )
    (net (code "119") (name "unconnected-(U$1-Pad75)") (class "Default")
      (node (ref "U$1") (pin "75") (pinfunction "75_75") (pintype "bidirectional"))
    )
    (net (code "120") (name "unconnected-(U$4-PG-Pad6)") (class "Default")
      (node (ref "U$4") (pin "6") (pinfunction "PG_6") (pintype "bidirectional"))
    )
    (net (code "121") (name "unconnected-(U$16-OC-Pad5)") (class "Default")
      (node (ref "U$16") (pin "5") (pinfunction "OC_5") (pintype "bidirectional"))
    )
    (net (code "122") (name "unconnected-(U$17-OC-Pad5)") (class "Default")
      (node (ref "U$17") (pin "5") (pinfunction "OC_5") (pintype "bidirectional"))
    )
    (net (code "123") (name "unconnected-(U$18-OC-Pad5)") (class "Default")
      (node (ref "U$18") (pin "5") (pinfunction "OC_5") (pintype "bidirectional"))
    )
    (net (code "124") (name "unconnected-(U$19-NC1-Pad1)") (class "Default")
      (node (ref "U$19") (pin "1") (pinfunction "NC1_1") (pintype "bidirectional"))
    )
    (net (code "125") (name "unconnected-(U$19-NC2-Pad5)") (class "Default")
      (node (ref "U$19") (pin "5") (pinfunction "NC2_5") (pintype "bidirectional"))
    )
    (net (code "126") (name "unconnected-(U$19-NC3-Pad6)") (class "Default")
      (node (ref "U$19") (pin "6") (pinfunction "NC3_6") (pintype "bidirectional"))
    )
  )
)
